# 3PDT_Board_wLED.net
KiCad netlist of a schematic drawn in EAGLE
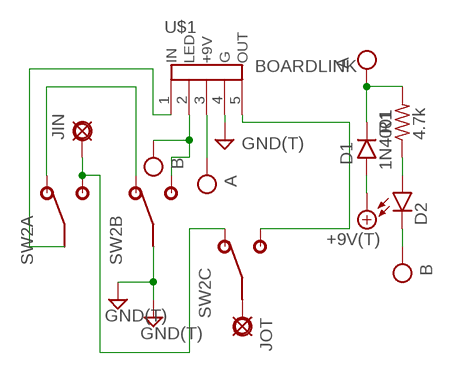
[diagram p0: schematic, sheet 1]

(export (version "E")
  (design (tool "Eeschema 10.0.6"))
  (components
    (comp (ref "+9V")
      (value "+9V(T)")
      (footprint "eagle-import:SQUARE")
      (libsource (lib "eagle-import") (part "+9V(T)"))
    )
    (comp (ref "D1")
      (value "1N4001")
      (footprint "eagle-import:DO41-3")
      (libsource (lib "eagle-import") (part "1N400X.3"))
    )
    (comp (ref "D2")
      (value "LED3MM")
      (footprint "eagle-import:LED3MM")
      (libsource (lib "eagle-import") (part "LED3MM"))
    )
    (comp (ref "G")
      (value "GND(T)")
      (footprint "eagle-import:SQUARE")
      (libsource (lib "eagle-import") (part "GND(T)"))
    )
    (comp (ref "JIG")
      (value "GND(T)")
      (footprint "eagle-import:SQUARE")
      (libsource (lib "eagle-import") (part "GND(T)"))
    )
    (comp (ref "JIN")
      (value "PAD")
      (footprint "eagle-import:SQUARE")
      (libsource (lib "eagle-import") (part "PAD"))
    )
    (comp (ref "JOG")
      (value "GND(T)")
      (footprint "eagle-import:SQUARE")
      (libsource (lib "eagle-import") (part "GND(T)"))
    )
    (comp (ref "JOT")
      (value "PAD")
      (footprint "eagle-import:SQUARE")
      (libsource (lib "eagle-import") (part "PAD"))
    )
    (comp (ref "R1")
      (value "4.7k")
      (footprint "eagle-import:R0207_3")
      (libsource (lib "eagle-import") (part "6MM.3"))
    )
    (comp (ref "SW2")
      (value "3PDT")
      (footprint "eagle-import:3PDT")
      (libsource (lib "eagle-import") (part "3PDT"))
    )
    (comp (ref "U$1")
      (value "BOARDLINK")
      (footprint "eagle-import:BOARDLINK")
      (libsource (lib "eagle-import") (part "BOARDLINK"))
    )
  )
  (nets
    (net (code "1") (name "+9V(T)") (class "Default")
      (node (ref "+9V") (pin "1") (pinfunction "+9V_1") (pintype "power_in"))
      (node (ref "D1") (pin "A") (pinfunction "A_A") (pintype "passive"))
    )
    (net (code "2") (name "A") (class "Default")
      (node (ref "D1") (pin "C") (pinfunction "C_C") (pintype "passive"))
      (node (ref "R1") (pin "2") (pinfunction "2_2") (pintype "passive"))
      (node (ref "U$1") (pin "3") (pinfunction "+9V_3") (pintype "bidirectional"))
    )
    (net (code "3") (name "B") (class "Default")
      (node (ref "D2") (pin "K") (pinfunction "C_K") (pintype "passive"))
      (node (ref "SW2") (pin "B3") (pinfunction "3_B3") (pintype "passive"))
      (node (ref "U$1") (pin "2") (pinfunction "LED_2") (pintype "bidirectional"))
    )
    (net (code "4") (name "GND(T)") (class "Default")
      (node (ref "G") (pin "1") (pinfunction "GND_1") (pintype "power_in"))
      (node (ref "JIG") (pin "1") (pinfunction "GND_1") (pintype "power_in"))
      (node (ref "JOG") (pin "1") (pinfunction "GND_1") (pintype "power_in"))
      (node (ref "SW2") (pin "B2") (pinfunction "2_B2") (pintype "passive"))
      (node (ref "U$1") (pin "4") (pinfunction "G_4") (pintype "bidirectional"))
    )
    (net (code "5") (name "Net-(D2-PadA)") (class "Default")
      (node (ref "D2") (pin "A") (pinfunction "A_A") (pintype "passive"))
      (node (ref "R1") (pin "1") (pinfunction "1_1") (pintype "passive"))
    )
    (net (code "6") (name "Net-(JIN-PAD)") (class "Default")
      (node (ref "JIN") (pin "1") (pinfunction "PAD_1") (pintype "passive"))
      (node (ref "SW2") (pin "A3") (pinfunction "3_A3") (pintype "passive"))
      (node (ref "SW2") (pin "C1") (pinfunction "1_C1") (pintype "passive"))
    )
    (net (code "7") (name "Net-(JOT-PAD)") (class "Default")
      (node (ref "JOT") (pin "1") (pinfunction "PAD_1") (pintype "passive"))
      (node (ref "SW2") (pin "C2") (pinfunction "2_C2") (pintype "passive"))
    )
    (net (code "8") (name "Net-(SW2A-1)") (class "Default")
      (node (ref "SW2") (pin "A1") (pinfunction "1_A1") (pintype "passive"))
      (node (ref "SW2") (pin "B1") (pinfunction "1_B1") (pintype "passive"))
    )
    (net (code "9") (name "Net-(SW2A-2)") (class "Default")
      (node (ref "SW2") (pin "A2") (pinfunction "2_A2") (pintype "passive"))
      (node (ref "U$1") (pin "1") (pinfunction "IN_1") (pintype "bidirectional"))
    )
    (net (code "10") (name "Net-(SW2C-3)") (class "Default")
      (node (ref "SW2") (pin "C3") (pinfunction "3_C3") (pintype "passive"))
      (node (ref "U$1") (pin "5") (pinfunction "OUT_5") (pintype "bidirectional"))
    )
  )
)
